# Motor_K.net
KiCad netlist of a schematic drawn in Altium Designer
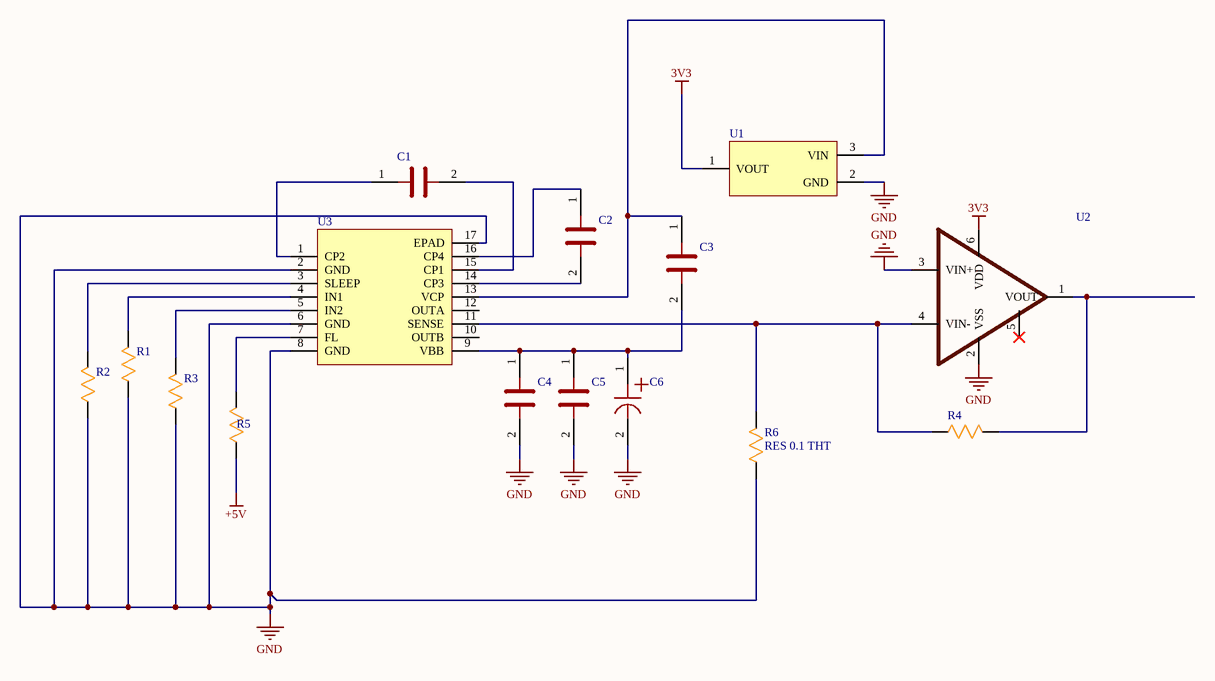
[diagram p0: Motor_K.SchDoc]

(export (version "E")
  (design (tool "Eeschema 10.0.6"))
  (components
    (comp (ref "C1")
      (value "CAP CER 0.1UF 10V X7R 0805")
      (footprint "CAP CER 0.1UF 10V X7R 0805")
      (description "Cap Ceramic 0.1uF 10V X7R 10% Pad SMD 0805 125C T/R")
      (fields
        (field (name "MANUFACTURER") "Wurth Electronics")
        (field (name "MANUFACTURER PART NUMBER") "885012207016")
        (field (name "DESIGNED BY") "ILKNUR")
      )
      (libsource (lib "Motor_K") (part "885012207016"))
    )
    (comp (ref "C2")
      (value "CAP CER 0.1UF 10V X7R 0805")
      (footprint "CAP CER 0.1UF 10V X7R 0805")
      (description "Cap Ceramic 0.1uF 10V X7R 10% Pad SMD 0805 125C T/R")
      (fields
        (field (name "MANUFACTURER") "Wurth Electronics")
        (field (name "MANUFACTURER PART NUMBER") "885012207016")
        (field (name "DESIGNED BY") "ILKNUR")
      )
      (libsource (lib "Motor_K") (part "885012207016"))
    )
    (comp (ref "C3")
      (value "CAP CER 0.1UF 10V X7R 0805")
      (footprint "CAP CER 0.1UF 10V X7R 0805")
      (description "Cap Ceramic 0.1uF 10V X7R 10% Pad SMD 0805 125C T/R")
      (fields
        (field (name "MANUFACTURER") "Wurth Electronics")
        (field (name "MANUFACTURER PART NUMBER") "885012207016")
        (field (name "DESIGNED BY") "ILKNUR")
      )
      (libsource (lib "Motor_K") (part "885012207016"))
    )
    (comp (ref "C4")
      (value "CAP CER 0.1UF 10V X7R 0805")
      (footprint "CAP CER 0.1UF 10V X7R 0805")
      (description "Cap Ceramic 0.1uF 10V X7R 10% Pad SMD 0805 125C T/R")
      (fields
        (field (name "MANUFACTURER") "Wurth Electronics")
        (field (name "MANUFACTURER PART NUMBER") "885012207016")
        (field (name "DESIGNED BY") "ILKNUR")
      )
      (libsource (lib "Motor_K") (part "885012207016"))
    )
    (comp (ref "C5")
      (value "CAP CER 10UF 10V X5R 0805")
      (footprint "CAP CER 10UF 10V X5R 0805")
      (description "Multilayer Ceramic Capacitor, 10 uF, 10 V, ± 10%, X5R, 0805 [2012 Metric]")
      (fields
        (field (name "MANUFACTURER") "Samsung")
        (field (name "MANUFACTURER PART NUMBER") "CL21A106KPCLQNC")
        (field (name "DESIGNED BY") "ILKNUR")
      )
      (libsource (lib "Motor_K") (part "CL21A106KPCLQNC"))
    )
    (comp (ref "C6")
      (value "CAP ALUM 10UF 20% 10V SMD")
      (footprint "CAP ALUM 10UF 20% 10V SMD")
      (description "Aluminum Electrolytic Capacitor, 10 uF, 10 V, ± 20%, 2000 hours @ 85°C, Radial Can - SMD")
      (fields
        (field (name "MANUFACTURER") "Panasonic")
        (field (name "MANUFACTURER PART NUMBER") "EEE-1AA100NR")
        (field (name "DESIGNED BY") "ILKNUR")
      )
      (libsource (lib "Motor_K") (part "EEE-1AA100NR"))
    )
    (comp (ref "R1")
      (value "RES 10K OHM 1% 1/8W 0805")
      (footprint "RES 10K OHM 1% 1/8W 0805")
      (description "SMD Chip Resistor, 10 kOhm, ± 1%, 125 mW, 0805 [2012 Metric], Thick Film, General Purpose")
      (fields
        (field (name "MANUFACTURER") "Yageo")
        (field (name "MANUFACTURER PART NUMBER") "RC0805FR-0710KL")
        (field (name "DESIGNED BY") "ILKNUR")
      )
      (libsource (lib "Motor_K") (part "RC0805FR-0710KL"))
    )
    (comp (ref "R2")
      (value "RES 10K OHM 1% 1/8W 0805")
      (footprint "RES 10K OHM 1% 1/8W 0805")
      (description "SMD Chip Resistor, 10 kOhm, ± 1%, 125 mW, 0805 [2012 Metric], Thick Film, General Purpose")
      (fields
        (field (name "MANUFACTURER") "Yageo")
        (field (name "MANUFACTURER PART NUMBER") "RC0805FR-0710KL")
        (field (name "DESIGNED BY") "ILKNUR")
      )
      (libsource (lib "Motor_K") (part "RC0805FR-0710KL"))
    )
    (comp (ref "R3")
      (value "RES 10K OHM 1% 1/8W 0805")
      (footprint "RES 10K OHM 1% 1/8W 0805")
      (description "SMD Chip Resistor, 10 kOhm, ± 1%, 125 mW, 0805 [2012 Metric], Thick Film, General Purpose")
      (fields
        (field (name "MANUFACTURER") "Yageo")
        (field (name "MANUFACTURER PART NUMBER") "RC0805FR-0710KL")
        (field (name "DESIGNED BY") "ILKNUR")
      )
      (libsource (lib "Motor_K") (part "RC0805FR-0710KL"))
    )
    (comp (ref "R4")
      (value "RES 10K OHM 1% 1/8W 0805")
      (footprint "RES 10K OHM 1% 1/8W 0805")
      (description "SMD Chip Resistor, 10 kOhm, ± 1%, 125 mW, 0805 [2012 Metric], Thick Film, General Purpose")
      (fields
        (field (name "MANUFACTURER") "Yageo")
        (field (name "MANUFACTURER PART NUMBER") "RC0805FR-0710KL")
        (field (name "DESIGNED BY") "ILKNUR")
      )
      (libsource (lib "Motor_K") (part "RC0805FR-0710KL"))
    )
    (comp (ref "R5")
      (value "RES 10K OHM 1% 1/8W 0805")
      (footprint "RES 10K OHM 1% 1/8W 0805")
      (description "SMD Chip Resistor, 10 kOhm, ± 1%, 125 mW, 0805 [2012 Metric], Thick Film, General Purpose")
      (fields
        (field (name "MANUFACTURER") "Yageo")
        (field (name "MANUFACTURER PART NUMBER") "RC0805FR-0710KL")
        (field (name "DESIGNED BY") "ILKNUR")
      )
      (libsource (lib "Motor_K") (part "RC0805FR-0710KL"))
    )
    (comp (ref "R6")
      (value "RES 0.1 THT")
      (footprint "111")
      (description "Resistors Metal Film Res 0.1 Ohms Pwr-Rtg 0.5 W Tol 5%Axial LR Neohm Series")
      (fields
        (field (name "MANUFACTURER") "TE Connectivity")
        (field (name "MANUFACTURER PART NUMBER") "1622598-1")
        (field (name "DESIGNED BY") "ILKNUR")
      )
      (libsource (lib "Motor_K") (part "LR1LJR10"))
    )
    (comp (ref "U1")
      (value "Regülatör 3.3v 100mA SOT89 ST")
      (footprint "SOT89")
      (description "Linear Voltage Regulator IC Positive Fixed 1 Output 3.3V 100mA SOT-89-3")
      (fields
        (field (name "MANUFACTURER") "STMicroelectronics")
        (field (name "MANUFACTURER PART NUMBER") "L78L33ABUTR")
        (field (name "DESIGNED BY") "ILKNUR")
      )
      (libsource (lib "Motor_K") (part "Regülatör 3.3v 100mA SOT89 ST"))
    )
    (comp (ref "U2")
      (value "IC Opamp GP 1 Circuit SOT23-6")
      (footprint "IC Opamp GP 1 Circuit SOT23-6")
      (description "MCP6043 Series 6 V 14 kHz Rail-to-Rail I/O Operational Amplifier -SOT-23-6")
      (fields
        (field (name "MANUFACTURER") "Microchip")
        (field (name "MANUFACTURER PART NUMBER") "MCP6043T-E/CH")
        (field (name "DESIGNED BY") "ILKNUR")
      )
      (libsource (lib "Motor_K") (part "IC Opamp GP 1 Circuit SOT23-6"))
    )
    (comp (ref "U3")
      (value "IC Motor Driver 2.5V-9V 16QFN")
      (footprint "IC Motor Driver 2.5V-9V")
      (description "1A Brush DC Motor 2.5V~9V Parallel QFN-16-EP(3x3) Motor Driver ICs ROHS")
      (fields
        (field (name "MANUFACTURER") "Allegro MicroSystems")
        (field (name "MANUFACTURER PART NUMBER") "A3918SESTR-T")
        (field (name "DESIGNED BY") "ILKNUR")
      )
      (libsource (lib "Motor_K") (part "IC Motor Driver 2.5V-9V 16QFN"))
    )
  )
  (nets
    (net (code "1") (name "+5V") (class "Default")
      (node (ref "R5") (pin "1") (pinfunction "1_1") (pintype "passive"))
    )
    (net (code "2") (name "3V3") (class "Default")
      (node (ref "U1") (pin "1") (pinfunction "VOUT_1") (pintype "passive"))
      (node (ref "U2") (pin "6") (pinfunction "VDD_6") (pintype "passive"))
    )
    (net (code "3") (name "GND") (class "Default")
      (node (ref "C4") (pin "2") (pinfunction "2_2") (pintype "passive"))
      (node (ref "C5") (pin "2") (pinfunction "2_2") (pintype "passive"))
      (node (ref "C6") (pin "2") (pinfunction "2_2") (pintype "passive"))
      (node (ref "R1") (pin "1") (pinfunction "1_1") (pintype "passive"))
      (node (ref "R2") (pin "1") (pinfunction "1_1") (pintype "passive"))
      (node (ref "R3") (pin "1") (pinfunction "1_1") (pintype "passive"))
      (node (ref "R6") (pin "1") (pinfunction "1_1") (pintype "passive"))
      (node (ref "U1") (pin "2") (pinfunction "GND_2") (pintype "passive"))
      (node (ref "U2") (pin "2") (pinfunction "VSS_2") (pintype "passive"))
      (node (ref "U2") (pin "3") (pinfunction "VIN+_3") (pintype "passive"))
      (node (ref "U3") (pin "17") (pinfunction "EPAD_17") (pintype "passive"))
      (node (ref "U3") (pin "2") (pinfunction "GND_2") (pintype "passive"))
      (node (ref "U3") (pin "6") (pinfunction "GND_6") (pintype "passive"))
      (node (ref "U3") (pin "8") (pinfunction "GND_8") (pintype "passive"))
    )
    (net (code "4") (name "Net-(U1-VIN)") (class "Default")
      (node (ref "C3") (pin "1") (pinfunction "1_1") (pintype "passive"))
      (node (ref "U1") (pin "3") (pinfunction "VIN_3") (pintype "passive"))
      (node (ref "U3") (pin "13") (pinfunction "VCP_13") (pintype "passive"))
    )
    (net (code "5") (name "Net-(U2-VIN-)") (class "Default")
      (node (ref "R4") (pin "1") (pinfunction "1_1") (pintype "passive"))
      (node (ref "R6") (pin "2") (pinfunction "2_2") (pintype "passive"))
      (node (ref "U2") (pin "4") (pinfunction "VIN-_4") (pintype "passive"))
      (node (ref "U3") (pin "11") (pinfunction "SENSE_11") (pintype "passive"))
    )
    (net (code "6") (name "Net-(U2-VOUT)") (class "Default")
      (node (ref "R4") (pin "2") (pinfunction "2_2") (pintype "passive"))
      (node (ref "U2") (pin "1") (pinfunction "VOUT_1") (pintype "passive"))
    )
    (net (code "7") (name "Net-(U3-CP1)") (class "Default")
      (node (ref "C1") (pin "2") (pinfunction "2_2") (pintype "passive"))
      (node (ref "U3") (pin "15") (pinfunction "CP1_15") (pintype "passive"))
    )
    (net (code "8") (name "Net-(U3-CP2)") (class "Default")
      (node (ref "C1") (pin "1") (pinfunction "1_1") (pintype "passive"))
      (node (ref "U3") (pin "1") (pinfunction "CP2_1") (pintype "passive"))
    )
    (net (code "9") (name "Net-(U3-CP3)") (class "Default")
      (node (ref "C2") (pin "2") (pinfunction "2_2") (pintype "passive"))
      (node (ref "U3") (pin "14") (pinfunction "CP3_14") (pintype "passive"))
    )
    (net (code "10") (name "Net-(U3-CP4)") (class "Default")
      (node (ref "C2") (pin "1") (pinfunction "1_1") (pintype "passive"))
      (node (ref "U3") (pin "16") (pinfunction "CP4_16") (pintype "passive"))
    )
    (net (code "11") (name "Net-(U3-FL)") (class "Default")
      (node (ref "R5") (pin "2") (pinfunction "2_2") (pintype "passive"))
      (node (ref "U3") (pin "7") (pinfunction "FL_7") (pintype "passive"))
    )
    (net (code "12") (name "Net-(U3-IN1)") (class "Default")
      (node (ref "R1") (pin "2") (pinfunction "2_2") (pintype "passive"))
      (node (ref "U3") (pin "4") (pinfunction "IN1_4") (pintype "passive"))
    )
    (net (code "13") (name "Net-(U3-IN2)") (class "Default")
      (node (ref "R3") (pin "2") (pinfunction "2_2") (pintype "passive"))
      (node (ref "U3") (pin "5") (pinfunction "IN2_5") (pintype "passive"))
    )
    (net (code "14") (name "Net-(U3-SLEEP)") (class "Default")
      (node (ref "R2") (pin "2") (pinfunction "2_2") (pintype "passive"))
      (node (ref "U3") (pin "3") (pinfunction "SLEEP_3") (pintype "passive"))
    )
    (net (code "15") (name "Net-(U3-VBB)") (class "Default")
      (node (ref "C3") (pin "2") (pinfunction "2_2") (pintype "passive"))
      (node (ref "C4") (pin "1") (pinfunction "1_1") (pintype "passive"))
      (node (ref "C5") (pin "1") (pinfunction "1_1") (pintype "passive"))
      (node (ref "C6") (pin "1") (pinfunction "1_1") (pintype "passive"))
      (node (ref "U3") (pin "9") (pinfunction "VBB_9") (pintype "passive"))
    )
    (net (code "16") (name "unconnected-(U2-CS-Pad5)") (class "Default")
      (node (ref "U2") (pin "5") (pinfunction "CS_5") (pintype "passive+no_connect"))
    )
    (net (code "17") (name "unconnected-(U3-OUTA-Pad12)") (class "Default")
      (node (ref "U3") (pin "12") (pinfunction "OUTA_12") (pintype "passive"))
    )
    (net (code "18") (name "unconnected-(U3-OUTB-Pad10)") (class "Default")
      (node (ref "U3") (pin "10") (pinfunction "OUTB_10") (pintype "passive"))
    )
  )
)
